# USB_HUB.net
KiCad netlist of a schematic drawn in Altium Designer
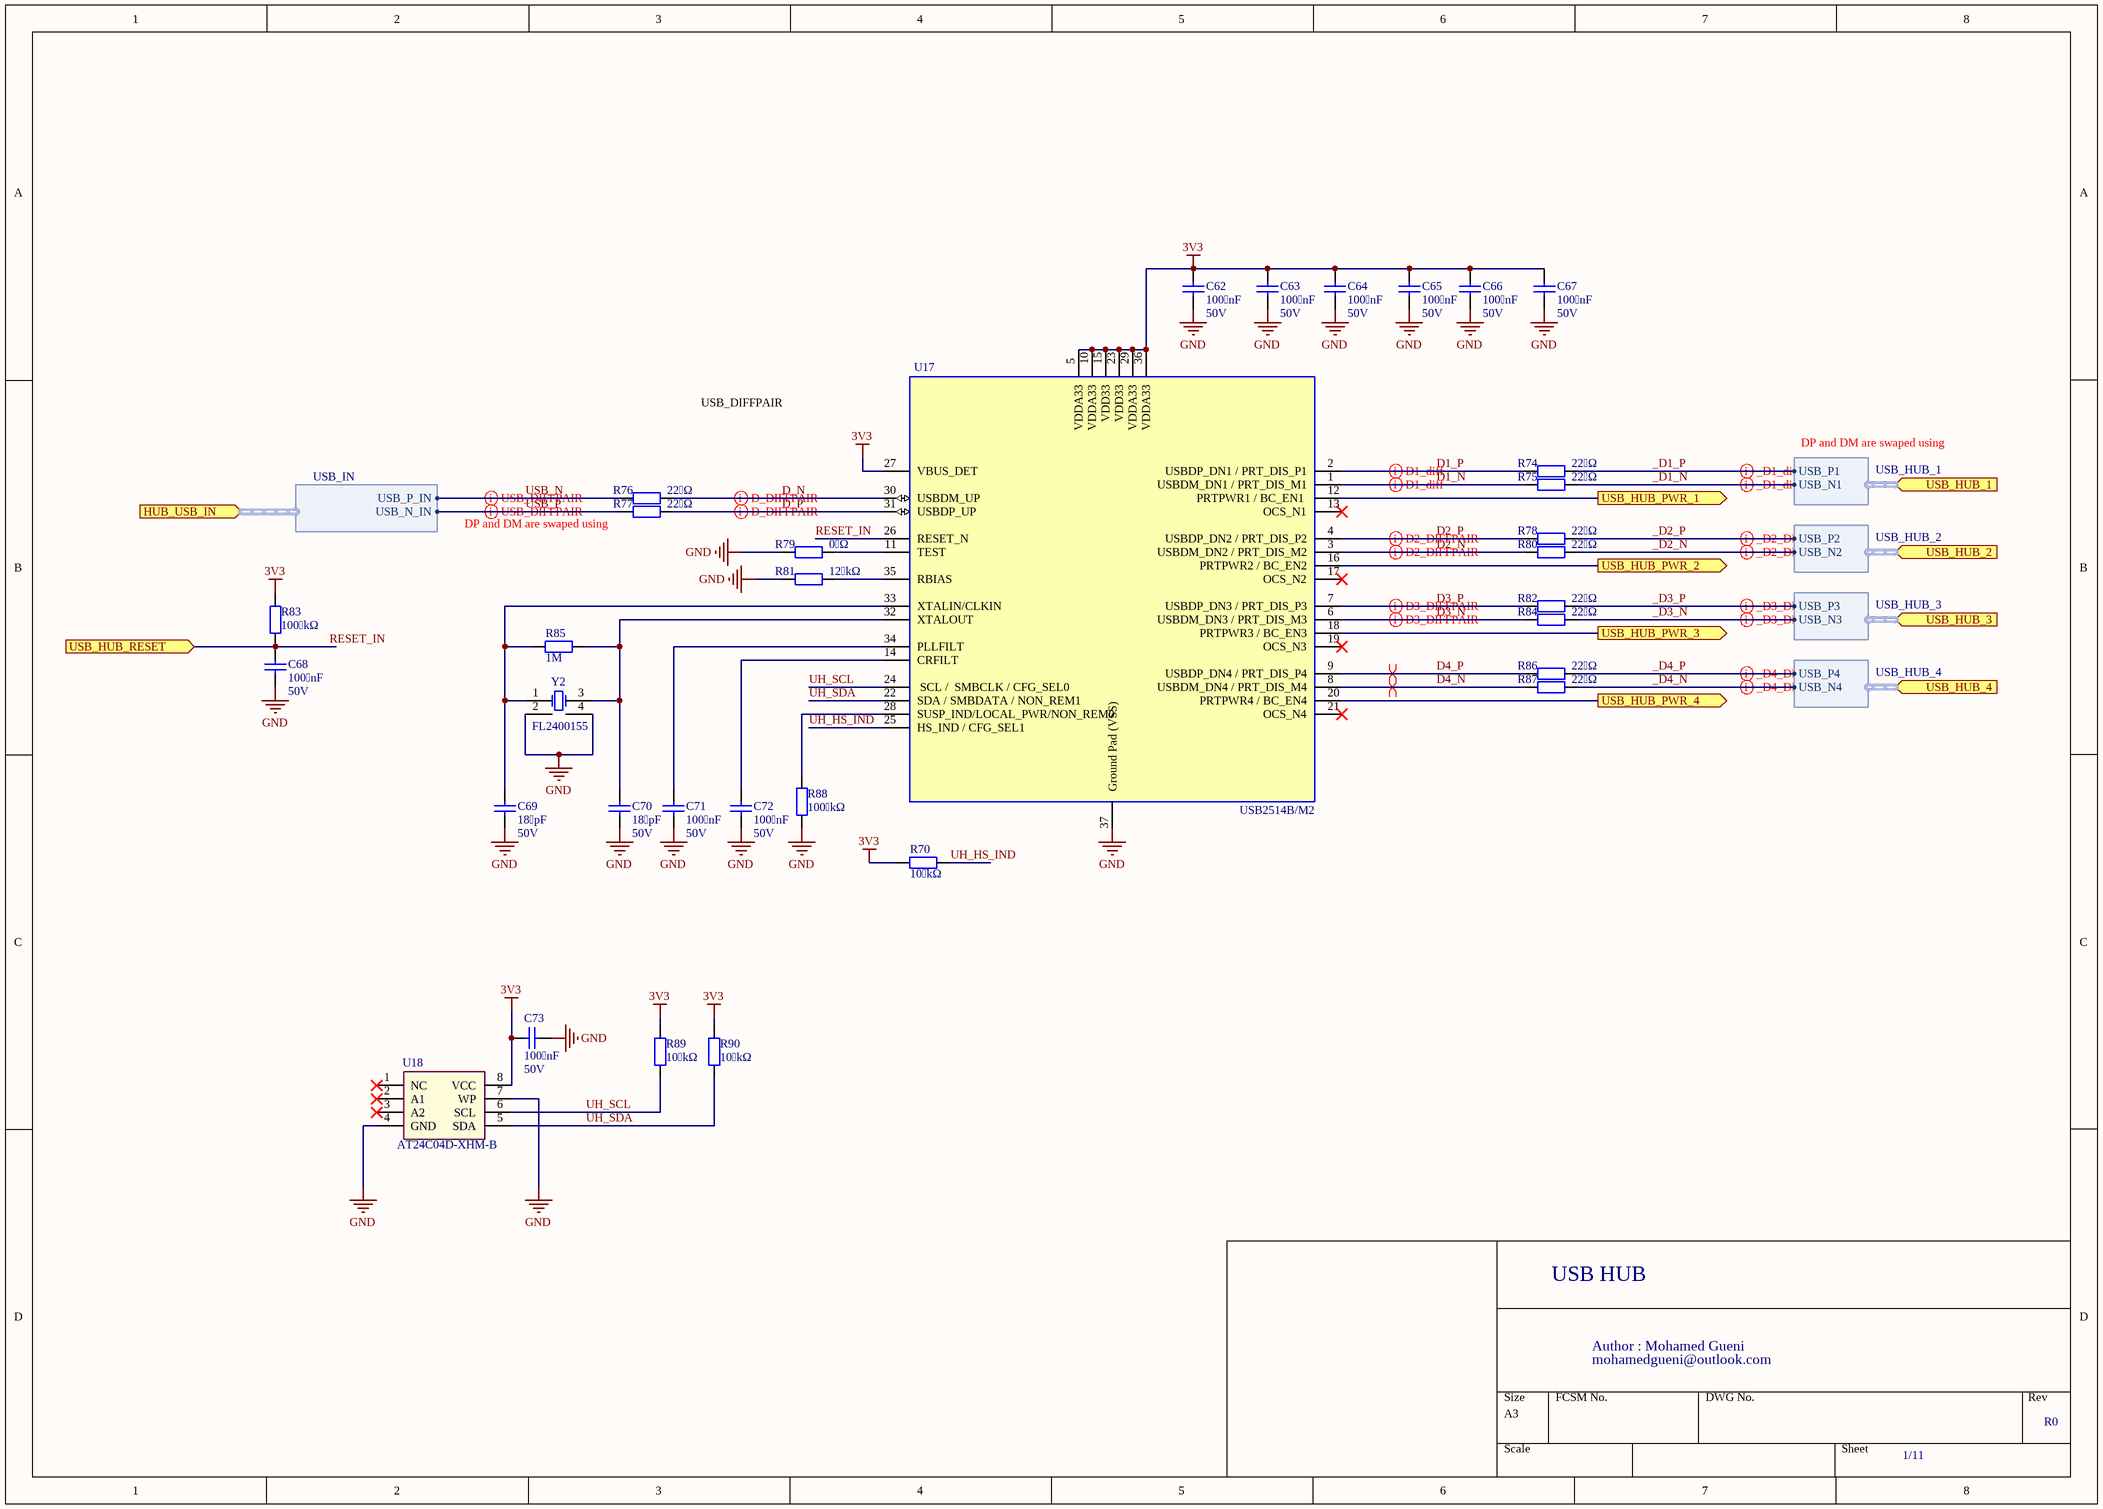
[diagram p0: USB HUB.SchDoc]

(export (version "E")
  (design (tool "Eeschema 10.0.6"))
  (components
    (comp (ref "C62")
      (value "GRM188R71H104KA93D")
      (footprint "CAPC1608N")
      (fields
        (field (name "PART NUMBER") "CAP-000000017")
        (field (name "VALUE 1") "100 nF")
        (field (name "VALUE 2") "50V")
      )
      (libsource (lib "DB") (part "Capacitor"))
    )
    (comp (ref "C63")
      (value "GRM188R71H104KA93D")
      (footprint "CAPC1608N")
      (fields
        (field (name "PART NUMBER") "CAP-000000017")
        (field (name "VALUE 1") "100 nF")
        (field (name "VALUE 2") "50V")
      )
      (libsource (lib "DB") (part "Capacitor"))
    )
    (comp (ref "C64")
      (value "GRM188R71H104KA93D")
      (footprint "CAPC1608N")
      (fields
        (field (name "PART NUMBER") "CAP-000000017")
        (field (name "VALUE 1") "100 nF")
        (field (name "VALUE 2") "50V")
      )
      (libsource (lib "DB") (part "Capacitor"))
    )
    (comp (ref "C65")
      (value "GRM188R71H104KA93D")
      (footprint "CAPC1608N")
      (fields
        (field (name "PART NUMBER") "CAP-000000017")
        (field (name "VALUE 1") "100 nF")
        (field (name "VALUE 2") "50V")
      )
      (libsource (lib "DB") (part "Capacitor"))
    )
    (comp (ref "C66")
      (value "GRM188R71H104KA93D")
      (footprint "CAPC1608N")
      (fields
        (field (name "PART NUMBER") "CAP-000000017")
        (field (name "VALUE 1") "100 nF")
        (field (name "VALUE 2") "50V")
      )
      (libsource (lib "DB") (part "Capacitor"))
    )
    (comp (ref "C67")
      (value "GRM188R71H104KA93D")
      (footprint "CAPC1608N")
      (fields
        (field (name "PART NUMBER") "CAP-000000017")
        (field (name "VALUE 1") "100 nF")
        (field (name "VALUE 2") "50V")
      )
      (libsource (lib "DB") (part "Capacitor"))
    )
    (comp (ref "C68")
      (value "GRM188R71H104KA93D")
      (footprint "CAPC1608N")
      (fields
        (field (name "PART NUMBER") "CAP-000000017")
        (field (name "VALUE 1") "100 nF")
        (field (name "VALUE 2") "50V")
      )
      (libsource (lib "DB") (part "Capacitor"))
    )
    (comp (ref "C69")
      (value "GRM1885C1H180JA01D")
      (footprint "CAPC1608N")
      (fields
        (field (name "PART NUMBER") "CAP-000000030")
        (field (name "VALUE 1") "18 pF")
        (field (name "VALUE 2") "50V")
      )
      (libsource (lib "DB") (part "Capacitor"))
    )
    (comp (ref "C70")
      (value "GRM1885C1H180JA01D")
      (footprint "CAPC1608N")
      (fields
        (field (name "PART NUMBER") "CAP-000000030")
        (field (name "VALUE 1") "18 pF")
        (field (name "VALUE 2") "50V")
      )
      (libsource (lib "DB") (part "Capacitor"))
    )
    (comp (ref "C71")
      (value "GRM188R71H104KA93D")
      (footprint "CAPC1608N")
      (fields
        (field (name "PART NUMBER") "CAP-000000017")
        (field (name "VALUE 1") "100 nF")
        (field (name "VALUE 2") "50V")
      )
      (libsource (lib "DB") (part "Capacitor"))
    )
    (comp (ref "C72")
      (value "GRM188R71H104KA93D")
      (footprint "CAPC1608N")
      (fields
        (field (name "PART NUMBER") "CAP-000000017")
        (field (name "VALUE 1") "100 nF")
        (field (name "VALUE 2") "50V")
      )
      (libsource (lib "DB") (part "Capacitor"))
    )
    (comp (ref "C73")
      (value "GRM188R71H104KA93D")
      (footprint "CAPC1608N")
      (fields
        (field (name "PART NUMBER") "CAP-000000017")
        (field (name "VALUE 1") "100 nF")
        (field (name "VALUE 2") "50V")
      )
      (libsource (lib "DB") (part "Capacitor"))
    )
    (comp (ref "R70")
      (value "CPF0603B10KE")
      (footprint "RESC1608N")
      (fields (field (name "PART NUMBER") "RES-0000000012") (field (name "VALUE 1") "10 kΩ"))
      (libsource (lib "DB") (part "Resistor"))
    )
    (comp (ref "R74")
      (value "ERJ-3EKF22R0V")
      (footprint "RESC1608N")
      (fields (field (name "PART NUMBER") "RES-0000000019") (field (name "VALUE 1") "22 Ω"))
      (libsource (lib "DB") (part "Resistor"))
    )
    (comp (ref "R75")
      (value "ERJ-3EKF22R0V")
      (footprint "RESC1608N")
      (fields (field (name "PART NUMBER") "RES-0000000019") (field (name "VALUE 1") "22 Ω"))
      (libsource (lib "DB") (part "Resistor"))
    )
    (comp (ref "R76")
      (value "ERJ-3EKF22R0V")
      (footprint "RESC1608N")
      (fields (field (name "PART NUMBER") "RES-0000000019") (field (name "VALUE 1") "22 Ω"))
      (libsource (lib "DB") (part "Resistor"))
    )
    (comp (ref "R77")
      (value "ERJ-3EKF22R0V")
      (footprint "RESC1608N")
      (fields (field (name "PART NUMBER") "RES-0000000019") (field (name "VALUE 1") "22 Ω"))
      (libsource (lib "DB") (part "Resistor"))
    )
    (comp (ref "R78")
      (value "ERJ-3EKF22R0V")
      (footprint "RESC1608N")
      (fields (field (name "PART NUMBER") "RES-0000000019") (field (name "VALUE 1") "22 Ω"))
      (libsource (lib "DB") (part "Resistor"))
    )
    (comp (ref "R79")
      (value "RMCF0603ZT0R00")
      (footprint "RESC1608N")
      (fields (field (name "PART NUMBER") "RES-0000000017") (field (name "VALUE 1") "0 Ω"))
      (libsource (lib "DB") (part "Resistor"))
    )
    (comp (ref "R80")
      (value "ERJ-3EKF22R0V")
      (footprint "RESC1608N")
      (fields (field (name "PART NUMBER") "RES-0000000019") (field (name "VALUE 1") "22 Ω"))
      (libsource (lib "DB") (part "Resistor"))
    )
    (comp (ref "R81")
      (value "ERJ-3EKF1202V")
      (footprint "RESC1608N")
      (fields (field (name "PART NUMBER") "RES-0000000011") (field (name "VALUE 1") "12 kΩ"))
      (libsource (lib "DB") (part "Resistor"))
    )
    (comp (ref "R82")
      (value "ERJ-3EKF22R0V")
      (footprint "RESC1608N")
      (fields (field (name "PART NUMBER") "RES-0000000019") (field (name "VALUE 1") "22 Ω"))
      (libsource (lib "DB") (part "Resistor"))
    )
    (comp (ref "R83")
      (value "TNPW0603100KBEA")
      (footprint "RESC1608N")
      (fields (field (name "PART NUMBER") "RES-0000000013") (field (name "VALUE 1") "100 kΩ"))
      (libsource (lib "") (part "Resistor_1"))
    )
    (comp (ref "R84")
      (value "ERJ-3EKF22R0V")
      (footprint "RESC1608N")
      (fields (field (name "PART NUMBER") "RES-0000000019") (field (name "VALUE 1") "22 Ω"))
      (libsource (lib "DB") (part "Resistor"))
    )
    (comp (ref "R85")
      (value "~")
      (footprint "RESC1608N")
      (fields (field (name "PART NUMBER") "RES-000000011") (field (name "VALUE 1") "1M"))
      (libsource (lib "DB") (part "Resistor"))
    )
    (comp (ref "R86")
      (value "ERJ-3EKF22R0V")
      (footprint "RESC1608N")
      (fields (field (name "PART NUMBER") "RES-0000000019") (field (name "VALUE 1") "22 Ω"))
      (libsource (lib "DB") (part "Resistor"))
    )
    (comp (ref "R87")
      (value "ERJ-3EKF22R0V")
      (footprint "RESC1608N")
      (fields (field (name "PART NUMBER") "RES-0000000019") (field (name "VALUE 1") "22 Ω"))
      (libsource (lib "DB") (part "Resistor"))
    )
    (comp (ref "R88")
      (value "TNPW0603100KBEA")
      (footprint "RESC1608N")
      (fields (field (name "PART NUMBER") "RES-0000000013") (field (name "VALUE 1") "100 kΩ"))
      (libsource (lib "") (part "Resistor_1"))
    )
    (comp (ref "R89")
      (value "CPF0603B10KE")
      (footprint "RESC1608N")
      (fields (field (name "PART NUMBER") "RES-0000000012") (field (name "VALUE 1") "10 kΩ"))
      (libsource (lib "") (part "Resistor_1"))
    )
    (comp (ref "R90")
      (value "CPF0603B10KE")
      (footprint "RESC1608N")
      (fields (field (name "PART NUMBER") "RES-0000000012") (field (name "VALUE 1") "10 kΩ"))
      (libsource (lib "") (part "Resistor_1"))
    )
    (comp (ref "U17")
      (value "USB2514B/M2")
      (footprint "SQFN-36")
      (fields (field (name "PART NUMBER") "GIC-000000002"))
      (libsource (lib "DB") (part "USB2514"))
    )
    (comp (ref "U18")
      (value "AT24C04D-XHM-B")
      (footprint "TSSOP-8AT24C04D-XHM-B")
      (fields (field (name "PART NUMBER") "GIC-000000011"))
      (libsource (lib "DB") (part "AT24C04D-XHM-B"))
    )
    (comp (ref "Y2")
      (value "FL2400155")
      (footprint "FL2400155")
      (fields (field (name "PART NUMBER") "Y-000000003"))
      (libsource (lib "DB") (part "XTAL_4"))
    )
  )
  (nets
    (net (code "6") (name "/D1_N") (class "Default")
      (node (ref "R75") (pin "2") (pinfunction "2_2") (pintype "passive"))
      (node (ref "U17") (pin "1") (pinfunction "USBDM_DN1_/_PRT_DIS_M1_1") (pintype "passive"))
    )
    (net (code "7") (name "/D1_P") (class "Default")
      (node (ref "R74") (pin "2") (pinfunction "2_2") (pintype "passive"))
      (node (ref "U17") (pin "2") (pinfunction "USBDP_DN1_/_PRT_DIS_P1_2") (pintype "passive"))
    )
    (net (code "8") (name "/D2_N") (class "Default")
      (node (ref "R80") (pin "2") (pinfunction "2_2") (pintype "passive"))
      (node (ref "U17") (pin "3") (pinfunction "USBDM_DN2_/_PRT_DIS_M2_3") (pintype "passive"))
    )
    (net (code "9") (name "/D2_P") (class "Default")
      (node (ref "R78") (pin "2") (pinfunction "2_2") (pintype "passive"))
      (node (ref "U17") (pin "4") (pinfunction "USBDP_DN2_/_PRT_DIS_P2_4") (pintype "passive"))
    )
    (net (code "10") (name "/D3_N") (class "Default")
      (node (ref "R84") (pin "2") (pinfunction "2_2") (pintype "passive"))
      (node (ref "U17") (pin "6") (pinfunction "USBDM_DN3_/_PRT_DIS_M3_6") (pintype "passive"))
    )
    (net (code "11") (name "/D3_P") (class "Default")
      (node (ref "R82") (pin "2") (pinfunction "2_2") (pintype "passive"))
      (node (ref "U17") (pin "7") (pinfunction "USBDP_DN3_/_PRT_DIS_P3_7") (pintype "passive"))
    )
    (net (code "12") (name "/D4_N") (class "Default")
      (node (ref "R87") (pin "2") (pinfunction "2_2") (pintype "passive"))
      (node (ref "U17") (pin "8") (pinfunction "USBDM_DN4_/_PRT_DIS_M4_8") (pintype "passive"))
    )
    (net (code "13") (name "/D4_P") (class "Default")
      (node (ref "R86") (pin "2") (pinfunction "2_2") (pintype "passive"))
      (node (ref "U17") (pin "9") (pinfunction "USBDP_DN4_/_PRT_DIS_P4_9") (pintype "passive"))
    )
    (net (code "14") (name "/D_N") (class "Default")
      (node (ref "R76") (pin "1") (pinfunction "1_1") (pintype "passive"))
      (node (ref "U17") (pin "30") (pinfunction "USBDM_UP_30") (pintype "bidirectional"))
    )
    (net (code "15") (name "/D_P") (class "Default")
      (node (ref "R77") (pin "1") (pinfunction "1_1") (pintype "passive"))
      (node (ref "U17") (pin "31") (pinfunction "USBDP_UP_31") (pintype "bidirectional"))
    )
    (net (code "16") (name "/RESET_IN") (class "Default")
      (node (ref "C68") (pin "2") (pinfunction "2_2") (pintype "passive"))
      (node (ref "R83") (pin "2") (pinfunction "2_2") (pintype "passive"))
      (node (ref "U17") (pin "26") (pinfunction "RESET_N_26") (pintype "passive"))
    )
    (net (code "17") (name "/UH_HS_IND") (class "Default")
      (node (ref "R70") (pin "1") (pinfunction "1_1") (pintype "passive"))
      (node (ref "U17") (pin "25") (pinfunction "HS_IND_/_CFG_SEL1_25") (pintype "passive"))
    )
    (net (code "18") (name "/UH_SCL") (class "Default")
      (node (ref "R89") (pin "2") (pinfunction "2_2") (pintype "passive"))
      (node (ref "U17") (pin "24") (pinfunction "_SCL_/__SMBCLK_/_CFG_SEL0_24") (pintype "passive"))
      (node (ref "U18") (pin "6") (pinfunction "SCL_6") (pintype "passive"))
    )
    (net (code "19") (name "/UH_SDA") (class "Default")
      (node (ref "R90") (pin "2") (pinfunction "2_2") (pintype "passive"))
      (node (ref "U17") (pin "22") (pinfunction "SDA_/_SMBDATA_/_NON_REM1_22") (pintype "passive"))
      (node (ref "U18") (pin "5") (pinfunction "SDA_5") (pintype "passive"))
    )
    (net (code "20") (name "/USB_HUB_PWR_1") (class "Default")
      (node (ref "U17") (pin "12") (pinfunction "PRTPWR1_/_BC_EN1_12") (pintype "passive"))
    )
    (net (code "21") (name "/USB_HUB_PWR_2") (class "Default")
      (node (ref "U17") (pin "16") (pinfunction "PRTPWR2_/_BC_EN2_16") (pintype "passive"))
    )
    (net (code "22") (name "/USB_HUB_PWR_3") (class "Default")
      (node (ref "U17") (pin "18") (pinfunction "PRTPWR3_/_BC_EN3_18") (pintype "passive"))
    )
    (net (code "23") (name "/USB_HUB_PWR_4") (class "Default")
      (node (ref "U17") (pin "20") (pinfunction "PRTPWR4_/_BC_EN4_20") (pintype "passive"))
    )
    (net (code "24") (name "/USB_N") (class "Default")
      (node (ref "R76") (pin "2") (pinfunction "2_2") (pintype "passive"))
    )
    (net (code "25") (name "/USB_P") (class "Default")
      (node (ref "R77") (pin "2") (pinfunction "2_2") (pintype "passive"))
    )
    (net (code "26") (name "/_D1_N") (class "Default")
      (node (ref "R75") (pin "1") (pinfunction "1_1") (pintype "passive"))
    )
    (net (code "27") (name "/_D1_P") (class "Default")
      (node (ref "R74") (pin "1") (pinfunction "1_1") (pintype "passive"))
    )
    (net (code "28") (name "/_D2_N") (class "Default")
      (node (ref "R80") (pin "1") (pinfunction "1_1") (pintype "passive"))
    )
    (net (code "29") (name "/_D2_P") (class "Default")
      (node (ref "R78") (pin "1") (pinfunction "1_1") (pintype "passive"))
    )
    (net (code "30") (name "/_D3_N") (class "Default")
      (node (ref "R84") (pin "1") (pinfunction "1_1") (pintype "passive"))
    )
    (net (code "31") (name "/_D3_P") (class "Default")
      (node (ref "R82") (pin "1") (pinfunction "1_1") (pintype "passive"))
    )
    (net (code "32") (name "/_D4_N") (class "Default")
      (node (ref "R87") (pin "1") (pinfunction "1_1") (pintype "passive"))
    )
    (net (code "33") (name "/_D4_P") (class "Default")
      (node (ref "R86") (pin "1") (pinfunction "1_1") (pintype "passive"))
    )
    (net (code "39") (name "3V3") (class "Default")
      (node (ref "C62") (pin "2") (pinfunction "2_2") (pintype "passive"))
      (node (ref "C63") (pin "2") (pinfunction "2_2") (pintype "passive"))
      (node (ref "C64") (pin "2") (pinfunction "2_2") (pintype "passive"))
      (node (ref "C65") (pin "2") (pinfunction "2_2") (pintype "passive"))
      (node (ref "C66") (pin "2") (pinfunction "2_2") (pintype "passive"))
      (node (ref "C67") (pin "2") (pinfunction "2_2") (pintype "passive"))
      (node (ref "C73") (pin "2") (pinfunction "2_2") (pintype "passive"))
      (node (ref "R70") (pin "2") (pinfunction "2_2") (pintype "passive"))
      (node (ref "R83") (pin "1") (pinfunction "1_1") (pintype "passive"))
      (node (ref "R89") (pin "1") (pinfunction "1_1") (pintype "passive"))
      (node (ref "R90") (pin "1") (pinfunction "1_1") (pintype "passive"))
      (node (ref "U17") (pin "10") (pinfunction "VDDA33_10") (pintype "passive"))
      (node (ref "U17") (pin "15") (pinfunction "VDD33_15") (pintype "passive"))
      (node (ref "U17") (pin "23") (pinfunction "VDD33_23") (pintype "passive"))
      (node (ref "U17") (pin "27") (pinfunction "VBUS_DET_27") (pintype "passive"))
      (node (ref "U17") (pin "29") (pinfunction "VDDA33_29") (pintype "passive"))
      (node (ref "U17") (pin "36") (pinfunction "VDDA33_36") (pintype "passive"))
      (node (ref "U17") (pin "5") (pinfunction "VDDA33_5") (pintype "passive"))
      (node (ref "U18") (pin "8") (pinfunction "VCC_8") (pintype "passive"))
    )
    (net (code "40") (name "GND") (class "Default")
      (node (ref "C62") (pin "1") (pinfunction "1_1") (pintype "passive"))
      (node (ref "C63") (pin "1") (pinfunction "1_1") (pintype "passive"))
      (node (ref "C64") (pin "1") (pinfunction "1_1") (pintype "passive"))
      (node (ref "C65") (pin "1") (pinfunction "1_1") (pintype "passive"))
      (node (ref "C66") (pin "1") (pinfunction "1_1") (pintype "passive"))
      (node (ref "C67") (pin "1") (pinfunction "1_1") (pintype "passive"))
      (node (ref "C68") (pin "1") (pinfunction "1_1") (pintype "passive"))
      (node (ref "C69") (pin "1") (pinfunction "1_1") (pintype "passive"))
      (node (ref "C70") (pin "1") (pinfunction "1_1") (pintype "passive"))
      (node (ref "C71") (pin "1") (pinfunction "1_1") (pintype "passive"))
      (node (ref "C72") (pin "1") (pinfunction "1_1") (pintype "passive"))
      (node (ref "C73") (pin "1") (pinfunction "1_1") (pintype "passive"))
      (node (ref "R79") (pin "2") (pinfunction "2_2") (pintype "passive"))
      (node (ref "R81") (pin "2") (pinfunction "2_2") (pintype "passive"))
      (node (ref "R88") (pin "2") (pinfunction "2_2") (pintype "passive"))
      (node (ref "U17") (pin "37") (pinfunction "Ground_Pad_(VSS)_37") (pintype "passive"))
      (node (ref "U18") (pin "4") (pinfunction "GND_4") (pintype "passive"))
      (node (ref "U18") (pin "7") (pinfunction "WP_7") (pintype "passive"))
      (node (ref "Y2") (pin "2") (pinfunction "Case1_2") (pintype "passive"))
      (node (ref "Y2") (pin "4") (pinfunction "Case2_4") (pintype "passive"))
    )
    (net (code "41") (name "Net-(U17-CRFILT)") (class "Default")
      (node (ref "C72") (pin "2") (pinfunction "2_2") (pintype "passive"))
      (node (ref "U17") (pin "14") (pinfunction "CRFILT_14") (pintype "passive"))
    )
    (net (code "42") (name "Net-(U17-PLLFILT)") (class "Default")
      (node (ref "C71") (pin "2") (pinfunction "2_2") (pintype "passive"))
      (node (ref "U17") (pin "34") (pinfunction "PLLFILT_34") (pintype "passive"))
    )
    (net (code "43") (name "Net-(U17-RBIAS)") (class "Default")
      (node (ref "R81") (pin "1") (pinfunction "1_1") (pintype "passive"))
      (node (ref "U17") (pin "35") (pinfunction "RBIAS_35") (pintype "passive"))
    )
    (net (code "44") (name "Net-(U17-SUSP_IND{slash}LOCAL_PWR{slash}NON_REM0)") (class "Default")
      (node (ref "R88") (pin "1") (pinfunction "1_1") (pintype "passive"))
      (node (ref "U17") (pin "28") (pinfunction "SUSP_IND/LOCAL_PWR/NON_REM0_28") (pintype "passive"))
    )
    (net (code "45") (name "Net-(U17-TEST)") (class "Default")
      (node (ref "R79") (pin "1") (pinfunction "1_1") (pintype "passive"))
      (node (ref "U17") (pin "11") (pinfunction "TEST_11") (pintype "passive"))
    )
    (net (code "46") (name "Net-(U17-XTALIN{slash}CLKIN)") (class "Default")
      (node (ref "C69") (pin "2") (pinfunction "2_2") (pintype "passive"))
      (node (ref "R85") (pin "2") (pinfunction "2_2") (pintype "passive"))
      (node (ref "U17") (pin "33") (pinfunction "XTALIN/CLKIN_33") (pintype "passive"))
      (node (ref "Y2") (pin "1") (pinfunction "OSC1_1") (pintype "passive"))
    )
    (net (code "47") (name "Net-(U17-XTALOUT)") (class "Default")
      (node (ref "C70") (pin "2") (pinfunction "2_2") (pintype "passive"))
      (node (ref "R85") (pin "1") (pinfunction "1_1") (pintype "passive"))
      (node (ref "U17") (pin "32") (pinfunction "XTALOUT_32") (pintype "passive"))
      (node (ref "Y2") (pin "3") (pinfunction "3_3") (pintype "passive"))
    )
    (net (code "48") (name "unconnected-(U17-OCS_N1-Pad13)") (class "Default")
      (node (ref "U17") (pin "13") (pinfunction "OCS_N1_13") (pintype "passive+no_connect"))
    )
    (net (code "49") (name "unconnected-(U17-OCS_N2-Pad17)") (class "Default")
      (node (ref "U17") (pin "17") (pinfunction "OCS_N2_17") (pintype "passive+no_connect"))
    )
    (net (code "50") (name "unconnected-(U17-OCS_N3-Pad19)") (class "Default")
      (node (ref "U17") (pin "19") (pinfunction "OCS_N3_19") (pintype "passive+no_connect"))
    )
    (net (code "51") (name "unconnected-(U17-OCS_N4-Pad21)") (class "Default")
      (node (ref "U17") (pin "21") (pinfunction "OCS_N4_21") (pintype "passive+no_connect"))
    )
    (net (code "52") (name "unconnected-(U18-A1-Pad2)") (class "Default")
      (node (ref "U18") (pin "2") (pinfunction "A1_2") (pintype "passive+no_connect"))
    )
    (net (code "53") (name "unconnected-(U18-A2-Pad3)") (class "Default")
      (node (ref "U18") (pin "3") (pinfunction "A2_3") (pintype "passive+no_connect"))
    )
    (net (code "54") (name "unconnected-(U18-NC-Pad1)") (class "Default")
      (node (ref "U18") (pin "1") (pinfunction "NC_1") (pintype "passive+no_connect"))
    )
  )
)
